# SODONGUYENLY.net
KiCad netlist of a schematic drawn in Altium Designer
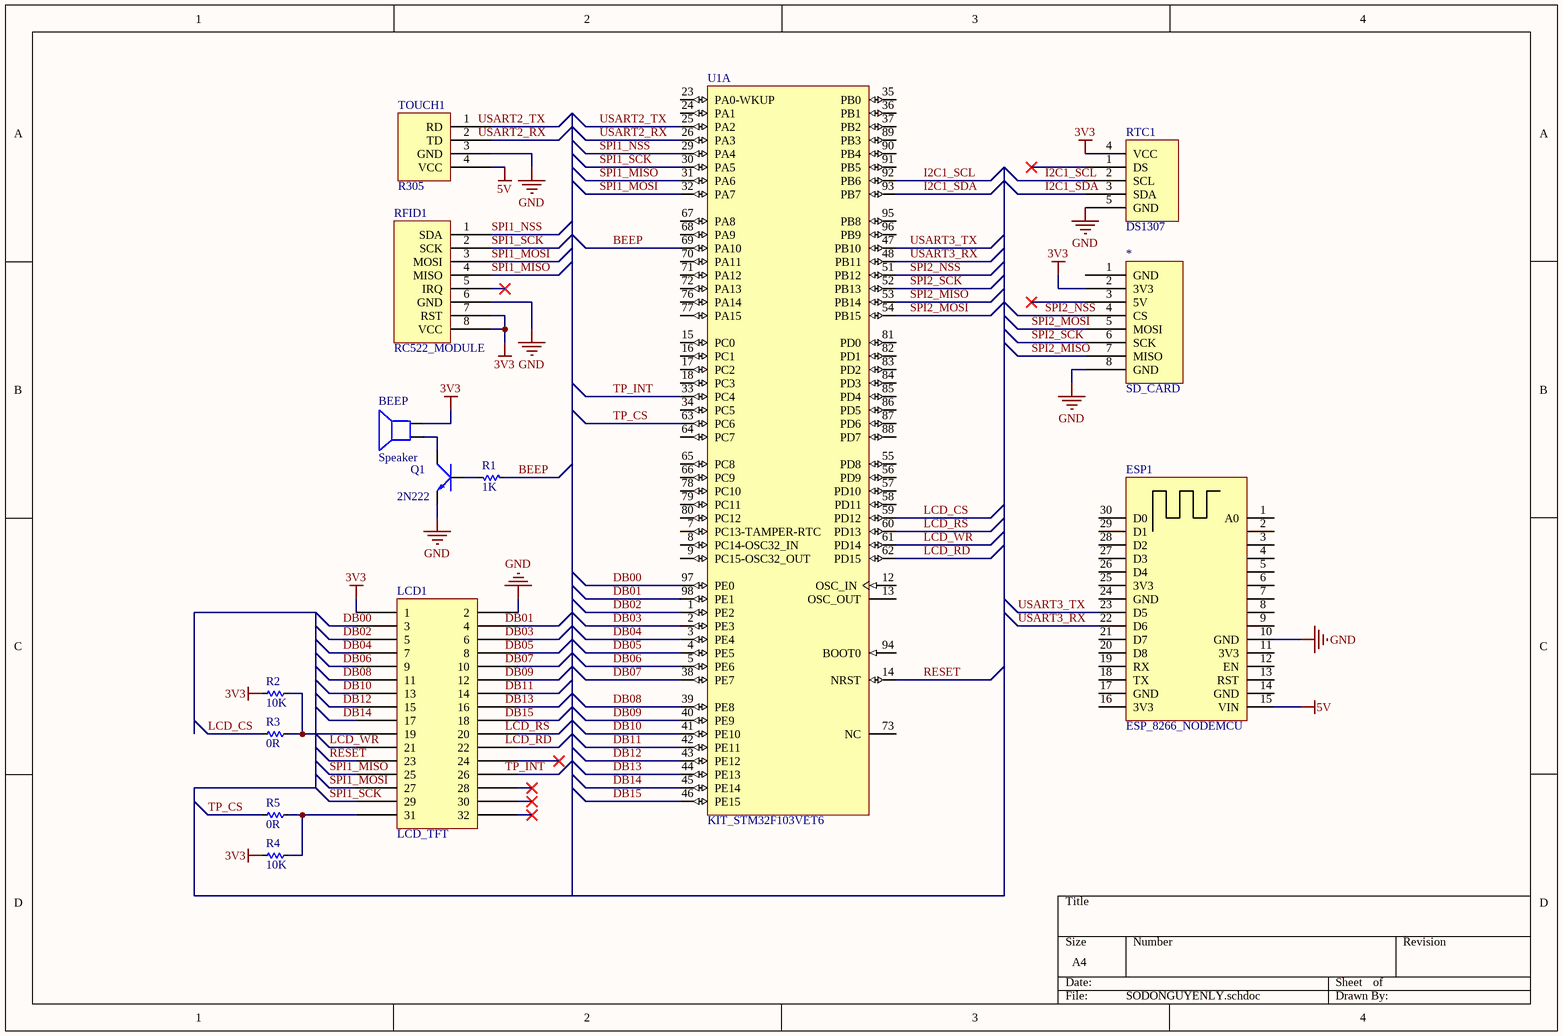
[diagram p0: SODONGUYENLY.schdoc]

(export (version "E")
  (design (tool "Eeschema 10.0.6"))
  (components
    (comp (ref "*") (value "SD_CARD") (libsource (lib "DATM_lib") (part "SD_CARD")))
    (comp (ref "BEEP")
      (value "Speaker")
      (footprint "SPEAKER")
      (description "Loudspeaker")
      (fields (field (name "PUBLISHER") "Altium Limited"))
      (libsource (lib "LIBRARY") (part "Speaker"))
    )
    (comp (ref "ESP1")
      (value "ESP_8266_NODEMCU")
      (footprint "Node MCU")
      (description "NodeMCU")
      (libsource (lib "hanguyen") (part "NodeMCU"))
    )
    (comp (ref "LCD1") (value "LCD_TFT") (libsource (lib "DATM_lib") (part "LCD")))
    (comp (ref "Q1")
      (value "2N222")
      (footprint "TO92-123")
      (description "NPN 600mW, ECB")
      (libsource (lib "LIBRARY") (part "2N222"))
    )
    (comp (ref "R1")
      (value "1K")
      (footprint "RES-1/2W")
      (description "Res")
      (fields
        (field (name "MANUFACTURER") "Generic Components")
        (field (name "PUBLISHER") "Altium Hobart Technology Centre")
      )
      (libsource (lib "LIBRARY") (part "Res"))
    )
    (comp (ref "R2")
      (value "10K")
      (footprint "RES-1/2W")
      (description "Res")
      (fields
        (field (name "MANUFACTURER") "Generic Components")
        (field (name "PUBLISHER") "Altium Hobart Technology Centre")
      )
      (libsource (lib "LIBRARY") (part "Res"))
    )
    (comp (ref "R3")
      (value "0R")
      (footprint "RES-1/2W")
      (description "Res")
      (fields
        (field (name "MANUFACTURER") "Generic Components")
        (field (name "PUBLISHER") "Altium Hobart Technology Centre")
      )
      (libsource (lib "LIBRARY") (part "Res"))
    )
    (comp (ref "R4")
      (value "10K")
      (footprint "RES-1/2W")
      (description "Res")
      (fields
        (field (name "MANUFACTURER") "Generic Components")
        (field (name "PUBLISHER") "Altium Hobart Technology Centre")
      )
      (libsource (lib "LIBRARY") (part "Res"))
    )
    (comp (ref "R5")
      (value "0R")
      (footprint "RES-1/2W")
      (description "Res")
      (fields
        (field (name "MANUFACTURER") "Generic Components")
        (field (name "PUBLISHER") "Altium Hobart Technology Centre")
      )
      (libsource (lib "LIBRARY") (part "Res"))
    )
    (comp (ref "RFID1") (value "RC522_MODULE") (libsource (lib "DATM_lib") (part "RFID")))
    (comp (ref "RTC1") (value "DS1307") (libsource (lib "DATM_lib") (part "DS1307_2")))
    (comp (ref "TOUCH1") (value "R305") (libsource (lib "DATM_lib") (part "R305")))
    (comp (ref "U1")
      (value "KIT_STM32F103VET6")
      (footprint "STM-LQFP100_N")
      (fields (field (name "PARTNUMBER") "STM32F103VET6"))
      (libsource (lib "STMicroelectronics STM32 F1") (part "STM32F103VET6"))
    )
  )
  (nets
    (net (code "1") (name "/BEEP") (class "Default")
      (node (ref "R1") (pin "2") (pinfunction "2_2") (pintype "passive"))
      (node (ref "U1") (pin "69") (pinfunction "PA10_69") (pintype "bidirectional"))
    )
    (net (code "2") (name "/DB00") (class "Default")
      (node (ref "LCD1") (pin "3") (pinfunction "3_3") (pintype "power_in"))
      (node (ref "U1") (pin "97") (pinfunction "PE0_97") (pintype "bidirectional"))
    )
    (net (code "3") (name "/DB01") (class "Default")
      (node (ref "U1") (pin "98") (pinfunction "PE1_98") (pintype "bidirectional"))
    )
    (net (code "4") (name "/DB02") (class "Default")
      (node (ref "LCD1") (pin "5") (pinfunction "5_5") (pintype "power_in"))
      (node (ref "U1") (pin "1") (pinfunction "PE2_1") (pintype "bidirectional"))
    )
    (net (code "5") (name "/DB03") (class "Default")
      (node (ref "U1") (pin "2") (pinfunction "PE3_2") (pintype "bidirectional"))
    )
    (net (code "6") (name "/DB04") (class "Default")
      (node (ref "LCD1") (pin "7") (pinfunction "7_7") (pintype "power_in"))
      (node (ref "U1") (pin "3") (pinfunction "PE4_3") (pintype "bidirectional"))
    )
    (net (code "7") (name "/DB05") (class "Default")
      (node (ref "U1") (pin "4") (pinfunction "PE5_4") (pintype "bidirectional"))
    )
    (net (code "8") (name "/DB06") (class "Default")
      (node (ref "LCD1") (pin "9") (pinfunction "9_9") (pintype "power_in"))
      (node (ref "U1") (pin "5") (pinfunction "PE6_5") (pintype "bidirectional"))
    )
    (net (code "9") (name "/DB07") (class "Default")
      (node (ref "U1") (pin "38") (pinfunction "PE7_38") (pintype "bidirectional"))
    )
    (net (code "10") (name "/DB08") (class "Default")
      (node (ref "LCD1") (pin "11") (pinfunction "11_11") (pintype "power_in"))
      (node (ref "U1") (pin "39") (pinfunction "PE8_39") (pintype "bidirectional"))
    )
    (net (code "11") (name "/DB09") (class "Default")
      (node (ref "U1") (pin "40") (pinfunction "PE9_40") (pintype "bidirectional"))
    )
    (net (code "12") (name "/DB10") (class "Default")
      (node (ref "LCD1") (pin "13") (pinfunction "13_13") (pintype "power_in"))
      (node (ref "U1") (pin "41") (pinfunction "PE10_41") (pintype "bidirectional"))
    )
    (net (code "13") (name "/DB11") (class "Default")
      (node (ref "U1") (pin "42") (pinfunction "PE11_42") (pintype "bidirectional"))
    )
    (net (code "14") (name "/DB12") (class "Default")
      (node (ref "LCD1") (pin "15") (pinfunction "15_15") (pintype "power_in"))
      (node (ref "U1") (pin "43") (pinfunction "PE12_43") (pintype "bidirectional"))
    )
    (net (code "15") (name "/DB13") (class "Default")
      (node (ref "U1") (pin "44") (pinfunction "PE13_44") (pintype "bidirectional"))
    )
    (net (code "16") (name "/DB14") (class "Default")
      (node (ref "LCD1") (pin "17") (pinfunction "17_17") (pintype "power_in"))
      (node (ref "U1") (pin "45") (pinfunction "PE14_45") (pintype "bidirectional"))
    )
    (net (code "17") (name "/DB15") (class "Default")
      (node (ref "U1") (pin "46") (pinfunction "PE15_46") (pintype "bidirectional"))
    )
    (net (code "18") (name "/I2C1_SCL") (class "Default")
      (node (ref "RTC1") (pin "2") (pinfunction "SCL_2") (pintype "power_in"))
      (node (ref "U1") (pin "92") (pinfunction "PB6_92") (pintype "bidirectional"))
    )
    (net (code "19") (name "/I2C1_SDA") (class "Default")
      (node (ref "RTC1") (pin "3") (pinfunction "SDA_3") (pintype "power_in"))
      (node (ref "U1") (pin "93") (pinfunction "PB7_93") (pintype "bidirectional"))
    )
    (net (code "20") (name "/LCD_CS") (class "Default")
      (node (ref "R3") (pin "2") (pinfunction "2_2") (pintype "passive"))
      (node (ref "U1") (pin "59") (pinfunction "PD12_59") (pintype "bidirectional"))
    )
    (net (code "21") (name "/LCD_RD") (class "Default")
      (node (ref "U1") (pin "62") (pinfunction "PD15_62") (pintype "bidirectional"))
    )
    (net (code "22") (name "/LCD_RS") (class "Default")
      (node (ref "U1") (pin "60") (pinfunction "PD13_60") (pintype "bidirectional"))
    )
    (net (code "23") (name "/LCD_WR") (class "Default")
      (node (ref "LCD1") (pin "21") (pinfunction "21_21") (pintype "power_in"))
      (node (ref "U1") (pin "61") (pinfunction "PD14_61") (pintype "bidirectional"))
    )
    (net (code "24") (name "/RESET") (class "Default")
      (node (ref "LCD1") (pin "23") (pinfunction "23_23") (pintype "power_in"))
      (node (ref "U1") (pin "14") (pinfunction "NRST_14") (pintype "bidirectional"))
    )
    (net (code "25") (name "/SPI1_MISO") (class "Default")
      (node (ref "LCD1") (pin "25") (pinfunction "25_25") (pintype "power_in"))
      (node (ref "RFID1") (pin "4") (pinfunction "MISO_4") (pintype "power_in"))
      (node (ref "U1") (pin "31") (pinfunction "PA6_31") (pintype "bidirectional"))
    )
    (net (code "26") (name "/SPI1_MOSI") (class "Default")
      (node (ref "LCD1") (pin "27") (pinfunction "27_27") (pintype "power_in"))
      (node (ref "RFID1") (pin "3") (pinfunction "MOSI_3") (pintype "power_in"))
      (node (ref "U1") (pin "32") (pinfunction "PA7_32") (pintype "bidirectional"))
    )
    (net (code "27") (name "/SPI1_NSS") (class "Default")
      (node (ref "RFID1") (pin "1") (pinfunction "SDA_1") (pintype "power_in"))
      (node (ref "U1") (pin "29") (pinfunction "PA4_29") (pintype "bidirectional"))
    )
    (net (code "28") (name "/SPI1_SCK") (class "Default")
      (node (ref "LCD1") (pin "29") (pinfunction "29_29") (pintype "power_in"))
      (node (ref "RFID1") (pin "2") (pinfunction "SCK_2") (pintype "power_in"))
      (node (ref "U1") (pin "30") (pinfunction "PA5_30") (pintype "bidirectional"))
    )
    (net (code "29") (name "/SPI2_MISO") (class "Default")
      (node (ref "*") (pin "7") (pinfunction "MISO_7") (pintype "power_in"))
      (node (ref "U1") (pin "53") (pinfunction "PB14_53") (pintype "bidirectional"))
    )
    (net (code "30") (name "/SPI2_MOSI") (class "Default")
      (node (ref "*") (pin "5") (pinfunction "MOSI_5") (pintype "power_in"))
      (node (ref "U1") (pin "54") (pinfunction "PB15_54") (pintype "bidirectional"))
    )
    (net (code "31") (name "/SPI2_NSS") (class "Default")
      (node (ref "*") (pin "4") (pinfunction "CS_4") (pintype "power_in"))
      (node (ref "U1") (pin "51") (pinfunction "PB12_51") (pintype "bidirectional"))
    )
    (net (code "32") (name "/SPI2_SCK") (class "Default")
      (node (ref "*") (pin "6") (pinfunction "SCK_6") (pintype "power_in"))
      (node (ref "U1") (pin "52") (pinfunction "PB13_52") (pintype "bidirectional"))
    )
    (net (code "33") (name "/TP_CS") (class "Default")
      (node (ref "R5") (pin "2") (pinfunction "2_2") (pintype "passive"))
      (node (ref "U1") (pin "63") (pinfunction "PC6_63") (pintype "bidirectional"))
    )
    (net (code "34") (name "/TP_INT") (class "Default")
      (node (ref "U1") (pin "33") (pinfunction "PC4_33") (pintype "bidirectional"))
    )
    (net (code "35") (name "/USART2_RX") (class "Default")
      (node (ref "U1") (pin "26") (pinfunction "PA3_26") (pintype "bidirectional"))
    )
    (net (code "36") (name "/USART2_TX") (class "Default")
      (node (ref "U1") (pin "25") (pinfunction "PA2_25") (pintype "bidirectional"))
    )
    (net (code "37") (name "/USART3_RX") (class "Default")
      (node (ref "ESP1") (pin "22") (pinfunction "D6_22") (pintype "passive"))
      (node (ref "U1") (pin "48") (pinfunction "PB11_48") (pintype "bidirectional"))
    )
    (net (code "38") (name "/USART3_TX") (class "Default")
      (node (ref "ESP1") (pin "23") (pinfunction "D5_23") (pintype "passive"))
      (node (ref "U1") (pin "47") (pinfunction "PB10_47") (pintype "bidirectional"))
    )
    (net (code "39") (name "3V3") (class "Default")
      (node (ref "*") (pin "2") (pinfunction "3V3_2") (pintype "power_in"))
      (node (ref "BEEP") (pin "1") (pinfunction "1_1") (pintype "passive"))
      (node (ref "LCD1") (pin "1") (pinfunction "1_1") (pintype "power_in"))
      (node (ref "R2") (pin "2") (pinfunction "2_2") (pintype "passive"))
      (node (ref "R4") (pin "2") (pinfunction "2_2") (pintype "passive"))
      (node (ref "RFID1") (pin "7") (pinfunction "RST_7") (pintype "power_in"))
      (node (ref "RFID1") (pin "8") (pinfunction "VCC_8") (pintype "power_in"))
      (node (ref "RTC1") (pin "4") (pinfunction "VCC_4") (pintype "power_in"))
    )
    (net (code "40") (name "5V") (class "Default")
      (node (ref "ESP1") (pin "15") (pinfunction "VIN_15") (pintype "passive"))
      (node (ref "TOUCH1") (pin "4") (pinfunction "VCC_4") (pintype "power_in"))
    )
    (net (code "41") (name "GND") (class "Default")
      (node (ref "*") (pin "8") (pinfunction "GND_8") (pintype "power_in"))
      (node (ref "ESP1") (pin "10") (pinfunction "GND_10") (pintype "passive"))
      (node (ref "LCD1") (pin "2") (pinfunction "2_2") (pintype "power_in"))
      (node (ref "Q1") (pin "1") (pinfunction "E_1") (pintype "passive"))
      (node (ref "RFID1") (pin "6") (pinfunction "GND_6") (pintype "power_in"))
      (node (ref "RTC1") (pin "5") (pinfunction "GND_5") (pintype "power_in"))
      (node (ref "TOUCH1") (pin "3") (pinfunction "GND_3") (pintype "power_in"))
    )
    (net (code "42") (name "Net-(LCD1-Pad19)") (class "Default")
      (node (ref "LCD1") (pin "19") (pinfunction "19_19") (pintype "power_in"))
      (node (ref "R2") (pin "1") (pinfunction "1_1") (pintype "passive"))
      (node (ref "R3") (pin "1") (pinfunction "1_1") (pintype "passive"))
    )
    (net (code "43") (name "Net-(LCD1-Pad31)") (class "Default")
      (node (ref "LCD1") (pin "31") (pinfunction "31_31") (pintype "power_in"))
      (node (ref "R4") (pin "1") (pinfunction "1_1") (pintype "passive"))
      (node (ref "R5") (pin "1") (pinfunction "1_1") (pintype "passive"))
    )
    (net (code "44") (name "Net-(Q1-B)") (class "Default")
      (node (ref "Q1") (pin "2") (pinfunction "B_2") (pintype "passive"))
      (node (ref "R1") (pin "1") (pinfunction "1_1") (pintype "passive"))
    )
    (net (code "45") (name "Net-(Q1-C)") (class "Default")
      (node (ref "BEEP") (pin "2") (pinfunction "2_2") (pintype "passive"))
      (node (ref "Q1") (pin "3") (pinfunction "C_3") (pintype "passive"))
    )
    (net (code "46") (name "unconnected-(*-5V-Pad3)") (class "Default")
      (node (ref "*") (pin "3") (pinfunction "5V_3") (pintype "power_in+no_connect"))
    )
    (net (code "47") (name "unconnected-(*-GND-Pad1)") (class "Default")
      (node (ref "*") (pin "1") (pinfunction "GND_1") (pintype "power_in"))
    )
    (net (code "48") (name "unconnected-(ESP1-3V3-Pad11)") (class "Default")
      (node (ref "ESP1") (pin "11") (pinfunction "3V3_11") (pintype "passive"))
    )
    (net (code "49") (name "unconnected-(ESP1-3V3-Pad16)") (class "Default")
      (node (ref "ESP1") (pin "16") (pinfunction "3V3_16") (pintype "passive"))
    )
    (net (code "50") (name "unconnected-(ESP1-3V3-Pad25)") (class "Default")
      (node (ref "ESP1") (pin "25") (pinfunction "3V3_25") (pintype "passive"))
    )
    (net (code "51") (name "unconnected-(ESP1-A0-Pad1)") (class "Default")
      (node (ref "ESP1") (pin "1") (pinfunction "A0_1") (pintype "passive"))
    )
    (net (code "52") (name "unconnected-(ESP1-D0-Pad30)") (class "Default")
      (node (ref "ESP1") (pin "30") (pinfunction "D0_30") (pintype "passive"))
    )
    (net (code "53") (name "unconnected-(ESP1-D1-Pad29)") (class "Default")
      (node (ref "ESP1") (pin "29") (pinfunction "D1_29") (pintype "passive"))
    )
    (net (code "54") (name "unconnected-(ESP1-D2-Pad28)") (class "Default")
      (node (ref "ESP1") (pin "28") (pinfunction "D2_28") (pintype "passive"))
    )
    (net (code "55") (name "unconnected-(ESP1-D3-Pad27)") (class "Default")
      (node (ref "ESP1") (pin "27") (pinfunction "D3_27") (pintype "passive"))
    )
    (net (code "56") (name "unconnected-(ESP1-D4-Pad26)") (class "Default")
      (node (ref "ESP1") (pin "26") (pinfunction "D4_26") (pintype "passive"))
    )
    (net (code "57") (name "unconnected-(ESP1-D7-Pad21)") (class "Default")
      (node (ref "ESP1") (pin "21") (pinfunction "D7_21") (pintype "passive"))
    )
    (net (code "58") (name "unconnected-(ESP1-D8-Pad20)") (class "Default")
      (node (ref "ESP1") (pin "20") (pinfunction "D8_20") (pintype "passive"))
    )
    (net (code "59") (name "unconnected-(ESP1-EN-Pad12)") (class "Default")
      (node (ref "ESP1") (pin "12") (pinfunction "EN_12") (pintype "passive"))
    )
    (net (code "60") (name "unconnected-(ESP1-GND-Pad14)") (class "Default")
      (node (ref "ESP1") (pin "14") (pinfunction "GND_14") (pintype "passive"))
    )
    (net (code "61") (name "unconnected-(ESP1-GND-Pad17)") (class "Default")
      (node (ref "ESP1") (pin "17") (pinfunction "GND_17") (pintype "passive"))
    )
    (net (code "62") (name "unconnected-(ESP1-GND-Pad24)") (class "Default")
      (node (ref "ESP1") (pin "24") (pinfunction "GND_24") (pintype "passive"))
    )
    (net (code "63") (name "unconnected-(ESP1-Pad2)") (class "Default")
      (node (ref "ESP1") (pin "2") (pintype "passive"))
    )
    (net (code "64") (name "unconnected-(ESP1-Pad3)") (class "Default")
      (node (ref "ESP1") (pin "3") (pintype "passive"))
    )
    (net (code "65") (name "unconnected-(ESP1-Pad4)") (class "Default")
      (node (ref "ESP1") (pin "4") (pintype "passive"))
    )
    (net (code "66") (name "unconnected-(ESP1-Pad5)") (class "Default")
      (node (ref "ESP1") (pin "5") (pintype "passive"))
    )
    (net (code "67") (name "unconnected-(ESP1-Pad6)") (class "Default")
      (node (ref "ESP1") (pin "6") (pintype "passive"))
    )
    (net (code "68") (name "unconnected-(ESP1-Pad7)") (class "Default")
      (node (ref "ESP1") (pin "7") (pintype "passive"))
    )
    (net (code "69") (name "unconnected-(ESP1-Pad8)") (class "Default")
      (node (ref "ESP1") (pin "8") (pintype "passive"))
    )
    (net (code "70") (name "unconnected-(ESP1-Pad9)") (class "Default")
      (node (ref "ESP1") (pin "9") (pintype "passive"))
    )
    (net (code "71") (name "unconnected-(ESP1-RST-Pad13)") (class "Default")
      (node (ref "ESP1") (pin "13") (pinfunction "RST_13") (pintype "passive"))
    )
    (net (code "72") (name "unconnected-(ESP1-RX-Pad19)") (class "Default")
      (node (ref "ESP1") (pin "19") (pinfunction "RX_19") (pintype "passive"))
    )
    (net (code "73") (name "unconnected-(ESP1-TX-Pad18)") (class "Default")
      (node (ref "ESP1") (pin "18") (pinfunction "TX_18") (pintype "passive"))
    )
    (net (code "74") (name "unconnected-(LCD1-Pad4)") (class "Default")
      (node (ref "LCD1") (pin "4") (pinfunction "4_4") (pintype "power_in"))
    )
    (net (code "75") (name "unconnected-(LCD1-Pad6)") (class "Default")
      (node (ref "LCD1") (pin "6") (pinfunction "6_6") (pintype "power_in"))
    )
    (net (code "76") (name "unconnected-(LCD1-Pad8)") (class "Default")
      (node (ref "LCD1") (pin "8") (pinfunction "8_8") (pintype "power_in"))
    )
    (net (code "77") (name "unconnected-(LCD1-Pad10)") (class "Default")
      (node (ref "LCD1") (pin "10") (pinfunction "10_10") (pintype "power_in"))
    )
    (net (code "78") (name "unconnected-(LCD1-Pad12)") (class "Default")
      (node (ref "LCD1") (pin "12") (pinfunction "12_12") (pintype "power_in"))
    )
    (net (code "79") (name "unconnected-(LCD1-Pad14)") (class "Default")
      (node (ref "LCD1") (pin "14") (pinfunction "14_14") (pintype "power_in"))
    )
    (net (code "80") (name "unconnected-(LCD1-Pad16)") (class "Default")
      (node (ref "LCD1") (pin "16") (pinfunction "16_16") (pintype "power_in"))
    )
    (net (code "81") (name "unconnected-(LCD1-Pad18)") (class "Default")
      (node (ref "LCD1") (pin "18") (pinfunction "18_18") (pintype "power_in"))
    )
    (net (code "82") (name "unconnected-(LCD1-Pad20)") (class "Default")
      (node (ref "LCD1") (pin "20") (pinfunction "20_20") (pintype "power_in"))
    )
    (net (code "83") (name "unconnected-(LCD1-Pad22)") (class "Default")
      (node (ref "LCD1") (pin "22") (pinfunction "22_22") (pintype "power_in"))
    )
    (net (code "84") (name "unconnected-(LCD1-Pad24)") (class "Default")
      (node (ref "LCD1") (pin "24") (pinfunction "24_24") (pintype "power_in+no_connect"))
    )
    (net (code "85") (name "unconnected-(LCD1-Pad26)") (class "Default")
      (node (ref "LCD1") (pin "26") (pinfunction "26_26") (pintype "power_in"))
    )
    (net (code "86") (name "unconnected-(LCD1-Pad28)") (class "Default")
      (node (ref "LCD1") (pin "28") (pinfunction "28_28") (pintype "power_in+no_connect"))
    )
    (net (code "87") (name "unconnected-(LCD1-Pad30)") (class "Default")
      (node (ref "LCD1") (pin "30") (pinfunction "30_30") (pintype "power_in+no_connect"))
    )
    (net (code "88") (name "unconnected-(LCD1-Pad32)") (class "Default")
      (node (ref "LCD1") (pin "32") (pinfunction "32_32") (pintype "power_in+no_connect"))
    )
    (net (code "89") (name "unconnected-(RFID1-IRQ-Pad5)") (class "Default")
      (node (ref "RFID1") (pin "5") (pinfunction "IRQ_5") (pintype "power_in+no_connect"))
    )
    (net (code "90") (name "unconnected-(RTC1-DS-Pad1)") (class "Default")
      (node (ref "RTC1") (pin "1") (pinfunction "DS_1") (pintype "power_in+no_connect"))
    )
    (net (code "91") (name "unconnected-(TOUCH1-RD-Pad1)") (class "Default")
      (node (ref "TOUCH1") (pin "1") (pinfunction "RD_1") (pintype "power_in"))
    )
    (net (code "92") (name "unconnected-(TOUCH1-TD-Pad2)") (class "Default")
      (node (ref "TOUCH1") (pin "2") (pinfunction "TD_2") (pintype "power_in"))
    )
    (net (code "93") (name "unconnected-(U1A-BOOT0-Pad94)") (class "Default")
      (node (ref "U1") (pin "94") (pinfunction "BOOT0_94") (pintype "input"))
    )
    (net (code "94") (name "unconnected-(U1A-NC-Pad73)") (class "Default")
      (node (ref "U1") (pin "73") (pinfunction "NC_73") (pintype "passive"))
    )
    (net (code "95") (name "unconnected-(U1A-OSC_IN-Pad12)") (class "Default")
      (node (ref "U1") (pin "12") (pinfunction "OSC_IN_12") (pintype "input"))
    )
    (net (code "96") (name "unconnected-(U1A-OSC_OUT-Pad13)") (class "Default")
      (node (ref "U1") (pin "13") (pinfunction "OSC_OUT_13") (pintype "passive"))
    )
    (net (code "97") (name "unconnected-(U1A-PA0-WKUP-Pad23)") (class "Default")
      (node (ref "U1") (pin "23") (pinfunction "PA0-WKUP_23") (pintype "bidirectional"))
    )
    (net (code "98") (name "unconnected-(U1A-PA1-Pad24)") (class "Default")
      (node (ref "U1") (pin "24") (pinfunction "PA1_24") (pintype "bidirectional"))
    )
    (net (code "99") (name "unconnected-(U1A-PA8-Pad67)") (class "Default")
      (node (ref "U1") (pin "67") (pinfunction "PA8_67") (pintype "bidirectional"))
    )
    (net (code "100") (name "unconnected-(U1A-PA9-Pad68)") (class "Default")
      (node (ref "U1") (pin "68") (pinfunction "PA9_68") (pintype "bidirectional"))
    )
    (net (code "101") (name "unconnected-(U1A-PA11-Pad70)") (class "Default")
      (node (ref "U1") (pin "70") (pinfunction "PA11_70") (pintype "bidirectional"))
    )
    (net (code "102") (name "unconnected-(U1A-PA12-Pad71)") (class "Default")
      (node (ref "U1") (pin "71") (pinfunction "PA12_71") (pintype "bidirectional"))
    )
    (net (code "103") (name "unconnected-(U1A-PA13-Pad72)") (class "Default")
      (node (ref "U1") (pin "72") (pinfunction "PA13_72") (pintype "bidirectional"))
    )
    (net (code "104") (name "unconnected-(U1A-PA14-Pad76)") (class "Default")
      (node (ref "U1") (pin "76") (pinfunction "PA14_76") (pintype "bidirectional"))
    )
    (net (code "105") (name "unconnected-(U1A-PA15-Pad77)") (class "Default")
      (node (ref "U1") (pin "77") (pinfunction "PA15_77") (pintype "bidirectional"))
    )
    (net (code "106") (name "unconnected-(U1A-PB0-Pad35)") (class "Default")
      (node (ref "U1") (pin "35") (pinfunction "PB0_35") (pintype "bidirectional"))
    )
    (net (code "107") (name "unconnected-(U1A-PB1-Pad36)") (class "Default")
      (node (ref "U1") (pin "36") (pinfunction "PB1_36") (pintype "bidirectional"))
    )
    (net (code "108") (name "unconnected-(U1A-PB2-Pad37)") (class "Default")
      (node (ref "U1") (pin "37") (pinfunction "PB2_37") (pintype "bidirectional"))
    )
    (net (code "109") (name "unconnected-(U1A-PB3-Pad89)") (class "Default")
      (node (ref "U1") (pin "89") (pinfunction "PB3_89") (pintype "bidirectional"))
    )
    (net (code "110") (name "unconnected-(U1A-PB4-Pad90)") (class "Default")
      (node (ref "U1") (pin "90") (pinfunction "PB4_90") (pintype "bidirectional"))
    )
    (net (code "111") (name "unconnected-(U1A-PB5-Pad91)") (class "Default")
      (node (ref "U1") (pin "91") (pinfunction "PB5_91") (pintype "bidirectional"))
    )
    (net (code "112") (name "unconnected-(U1A-PB8-Pad95)") (class "Default")
      (node (ref "U1") (pin "95") (pinfunction "PB8_95") (pintype "bidirectional"))
    )
    (net (code "113") (name "unconnected-(U1A-PB9-Pad96)") (class "Default")
      (node (ref "U1") (pin "96") (pinfunction "PB9_96") (pintype "bidirectional"))
    )
    (net (code "114") (name "unconnected-(U1A-PC0-Pad15)") (class "Default")
      (node (ref "U1") (pin "15") (pinfunction "PC0_15") (pintype "bidirectional"))
    )
    (net (code "115") (name "unconnected-(U1A-PC1-Pad16)") (class "Default")
      (node (ref "U1") (pin "16") (pinfunction "PC1_16") (pintype "bidirectional"))
    )
    (net (code "116") (name "unconnected-(U1A-PC2-Pad17)") (class "Default")
      (node (ref "U1") (pin "17") (pinfunction "PC2_17") (pintype "bidirectional"))
    )
    (net (code "117") (name "unconnected-(U1A-PC3-Pad18)") (class "Default")
      (node (ref "U1") (pin "18") (pinfunction "PC3_18") (pintype "bidirectional"))
    )
    (net (code "118") (name "unconnected-(U1A-PC5-Pad34)") (class "Default")
      (node (ref "U1") (pin "34") (pinfunction "PC5_34") (pintype "bidirectional"))
    )
    (net (code "119") (name "unconnected-(U1A-PC7-Pad64)") (class "Default")
      (node (ref "U1") (pin "64") (pinfunction "PC7_64") (pintype "bidirectional"))
    )
    (net (code "120") (name "unconnected-(U1A-PC8-Pad65)") (class "Default")
      (node (ref "U1") (pin "65") (pinfunction "PC8_65") (pintype "bidirectional"))
    )
    (net (code "121") (name "unconnected-(U1A-PC9-Pad66)") (class "Default")
      (node (ref "U1") (pin "66") (pinfunction "PC9_66") (pintype "bidirectional"))
    )
    (net (code "122") (name "unconnected-(U1A-PC10-Pad78)") (class "Default")
      (node (ref "U1") (pin "78") (pinfunction "PC10_78") (pintype "bidirectional"))
    )
    (net (code "123") (name "unconnected-(U1A-PC11-Pad79)") (class "Default")
      (node (ref "U1") (pin "79") (pinfunction "PC11_79") (pintype "bidirectional"))
    )
    (net (code "124") (name "unconnected-(U1A-PC12-Pad80)") (class "Default")
      (node (ref "U1") (pin "80") (pinfunction "PC12_80") (pintype "bidirectional"))
    )
    (net (code "125") (name "unconnected-(U1A-PC13-TAMPER-RTC-Pad7)") (class "Default")
      (node (ref "U1") (pin "7") (pinfunction "PC13-TAMPER-RTC_7") (pintype "bidirectional"))
    )
    (net (code "126") (name "unconnected-(U1A-PC14-OSC32_IN-Pad8)") (class "Default")
      (node (ref "U1") (pin "8") (pinfunction "PC14-OSC32_IN_8") (pintype "bidirectional"))
    )
    (net (code "127") (name "unconnected-(U1A-PC15-OSC32_OUT-Pad9)") (class "Default")
      (node (ref "U1") (pin "9") (pinfunction "PC15-OSC32_OUT_9") (pintype "bidirectional"))
    )
    (net (code "128") (name "unconnected-(U1A-PD0-Pad81)") (class "Default")
      (node (ref "U1") (pin "81") (pinfunction "PD0_81") (pintype "bidirectional"))
    )
    (net (code "129") (name "unconnected-(U1A-PD1-Pad82)") (class "Default")
      (node (ref "U1") (pin "82") (pinfunction "PD1_82") (pintype "bidirectional"))
    )
    (net (code "130") (name "unconnected-(U1A-PD2-Pad83)") (class "Default")
      (node (ref "U1") (pin "83") (pinfunction "PD2_83") (pintype "bidirectional"))
    )
    (net (code "131") (name "unconnected-(U1A-PD3-Pad84)") (class "Default")
      (node (ref "U1") (pin "84") (pinfunction "PD3_84") (pintype "bidirectional"))
    )
    (net (code "132") (name "unconnected-(U1A-PD4-Pad85)") (class "Default")
      (node (ref "U1") (pin "85") (pinfunction "PD4_85") (pintype "bidirectional"))
    )
    (net (code "133") (name "unconnected-(U1A-PD5-Pad86)") (class "Default")
      (node (ref "U1") (pin "86") (pinfunction "PD5_86") (pintype "bidirectional"))
    )
    (net (code "134") (name "unconnected-(U1A-PD6-Pad87)") (class "Default")
      (node (ref "U1") (pin "87") (pinfunction "PD6_87") (pintype "bidirectional"))
    )
    (net (code "135") (name "unconnected-(U1A-PD7-Pad88)") (class "Default")
      (node (ref "U1") (pin "88") (pinfunction "PD7_88") (pintype "bidirectional"))
    )
    (net (code "136") (name "unconnected-(U1A-PD8-Pad55)") (class "Default")
      (node (ref "U1") (pin "55") (pinfunction "PD8_55") (pintype "bidirectional"))
    )
    (net (code "137") (name "unconnected-(U1A-PD9-Pad56)") (class "Default")
      (node (ref "U1") (pin "56") (pinfunction "PD9_56") (pintype "bidirectional"))
    )
    (net (code "138") (name "unconnected-(U1A-PD10-Pad57)") (class "Default")
      (node (ref "U1") (pin "57") (pinfunction "PD10_57") (pintype "bidirectional"))
    )
    (net (code "139") (name "unconnected-(U1A-PD11-Pad58)") (class "Default")
      (node (ref "U1") (pin "58") (pinfunction "PD11_58") (pintype "bidirectional"))
    )
  )
)
